# A4a_Pro_Mini.net
KiCad netlist of a schematic drawn in EAGLE
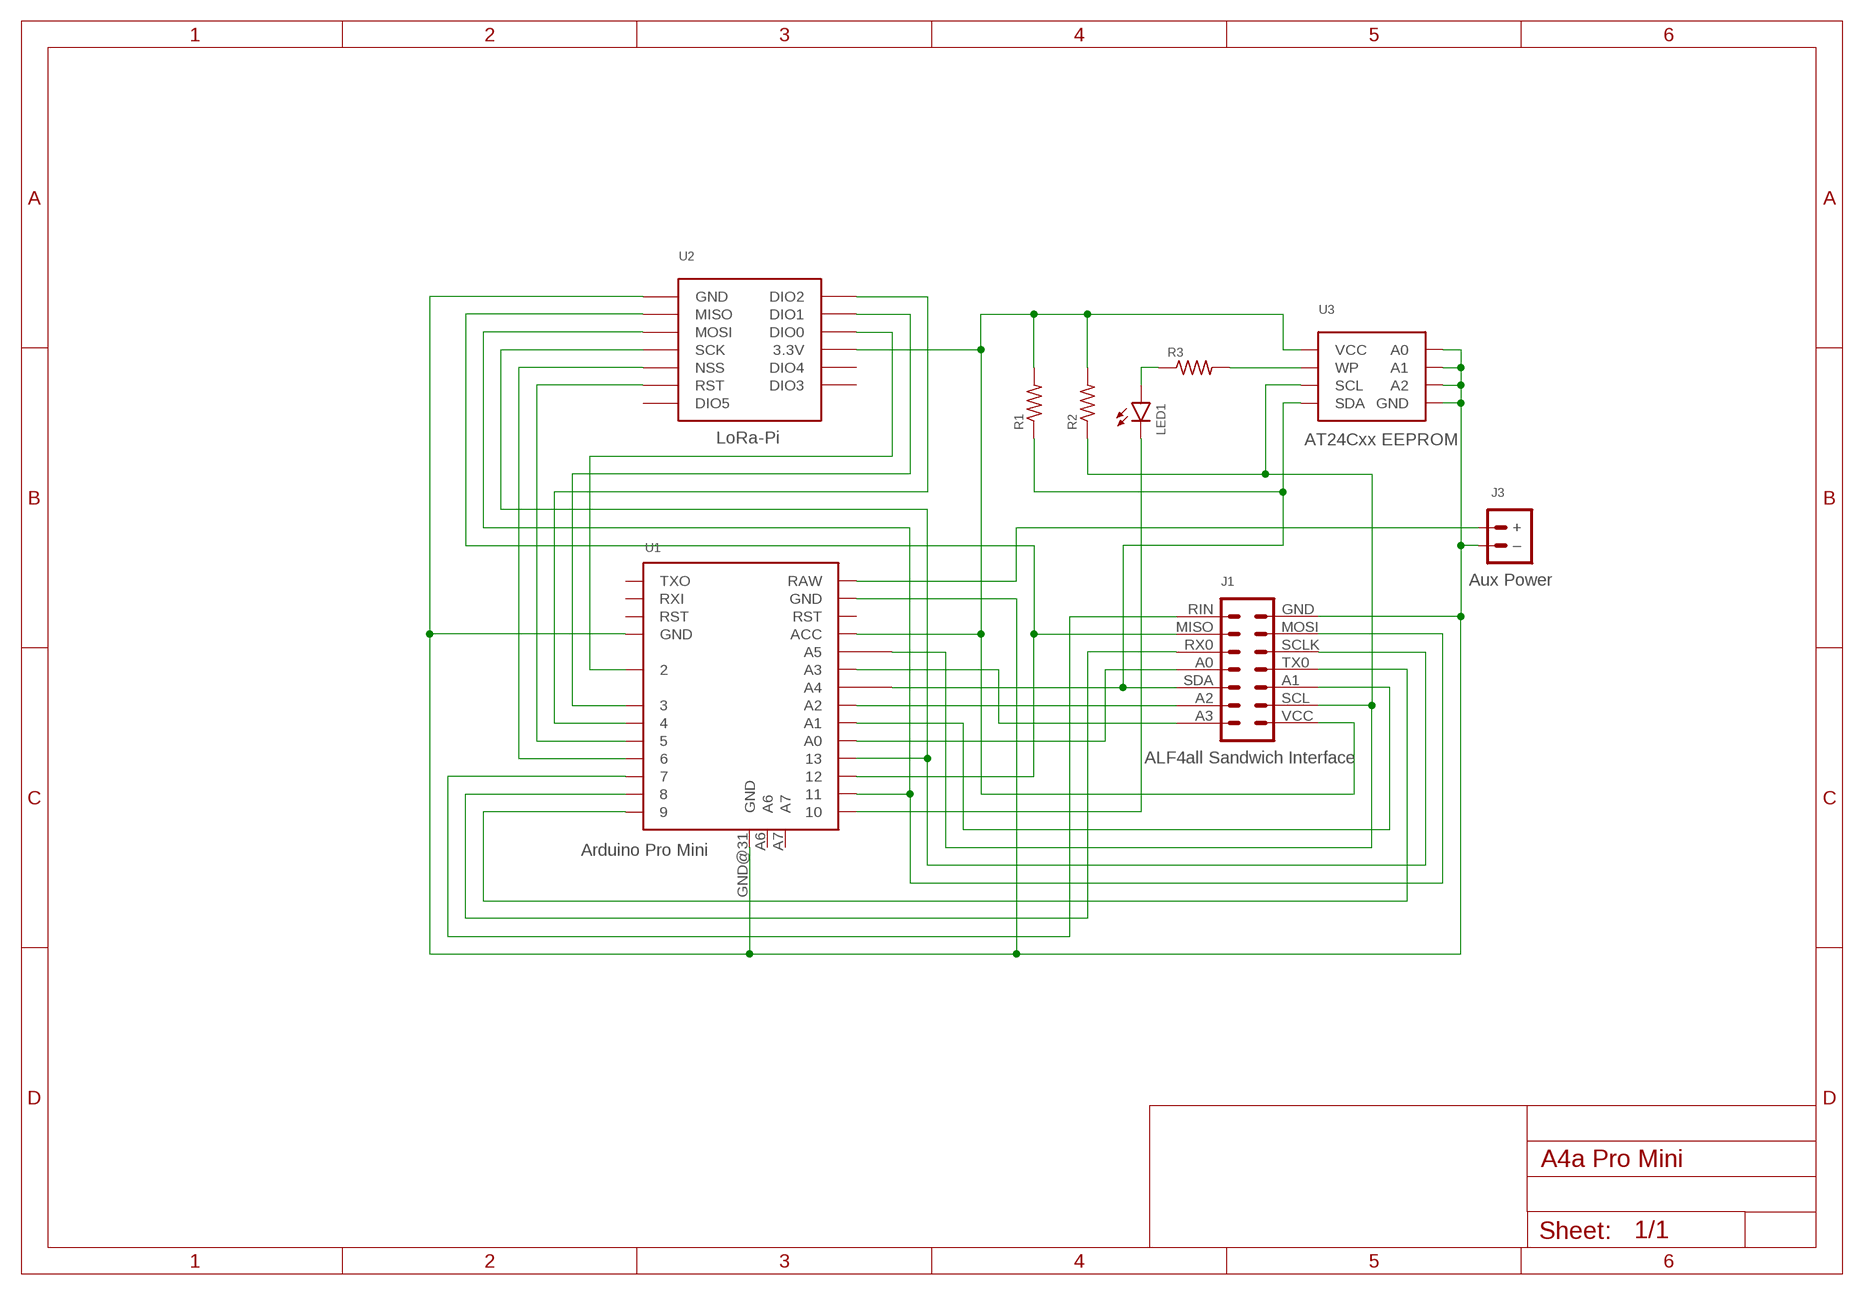
[diagram p0: schematic, sheet 1]

(export (version "E")
  (design (tool "Eeschema 10.0.6"))
  (components
    (comp (ref "J1")
      (value "ALF4all Sandwich Interface")
      (footprint "eagle-import:CONN_2X7-ALF4ALL-PROCESSOR-B")
      (libsource (lib "eagle-import") (part "HEADER-2X7-ALF4ALL-PROCESSOR-B"))
    )
    (comp (ref "J3")
      (value "Aux Power")
      (footprint "eagle-import:JST-PH2.0-2-HORIZONTAL")
      (libsource (lib "eagle-import") (part "JST-PH2.0-2-MALE-HORIZONTALJST-PTH-2"))
    )
    (comp (ref "LED1")
      (value "LEDCHIP-LED0805")
      (footprint "eagle-import:CHIP-LED0805")
      (libsource (lib "eagle-import") (part "LEDCHIP-LED0805"))
    )
    (comp (ref "R1")
      (value "RESISTORR0805")
      (footprint "eagle-import:R0805")
      (libsource (lib "eagle-import") (part "RESISTORR0805"))
    )
    (comp (ref "R2")
      (value "RESISTORR0805")
      (footprint "eagle-import:R0805")
      (libsource (lib "eagle-import") (part "RESISTORR0805"))
    )
    (comp (ref "R3")
      (value "RESISTORR0805")
      (footprint "eagle-import:R0805")
      (libsource (lib "eagle-import") (part "RESISTORR0805"))
    )
    (comp (ref "U1")
      (value "Arduino Pro Mini")
      (footprint "eagle-import:ARDUINO-PRO-MINI-35")
      (libsource (lib "eagle-import") (part "ARDUINO-PRO-MINI-35"))
    )
    (comp (ref "U2")
      (value "LoRa-Pi")
      (footprint "eagle-import:RFM95W-PI")
      (libsource (lib "eagle-import") (part "RFM95W-PI"))
    )
    (comp (ref "U3")
      (value "AT24Cxx EEPROM")
      (footprint "eagle-import:SOP-8")
      (libsource (lib "eagle-import") (part "AT24CXX-EEPROM"))
    )
  )
  (nets
    (net (code "1") (name "Net-(J1-1)") (class "Default")
      (node (ref "J1") (pin "VCC") (pinfunction "1_VCC") (pintype "passive"))
      (node (ref "R1") (pin "2") (pinfunction "2_2") (pintype "passive"))
      (node (ref "R2") (pin "2") (pinfunction "2_2") (pintype "passive"))
      (node (ref "U1") (pin "ACC") (pinfunction "ACC_ACC") (pintype "bidirectional"))
      (node (ref "U2") (pin "3V3") (pinfunction "3.3V_3V3") (pintype "power_in"))
      (node (ref "U3") (pin "P$8") (pinfunction "VCC_P$8") (pintype "bidirectional"))
    )
    (net (code "2") (name "Net-(J1-2)") (class "Default")
      (node (ref "J1") (pin "SCL") (pinfunction "2_SCL") (pintype "passive"))
      (node (ref "R2") (pin "1") (pinfunction "1_1") (pintype "passive"))
      (node (ref "U1") (pin "A5") (pinfunction "A5_A5") (pintype "bidirectional"))
      (node (ref "U3") (pin "P$6") (pinfunction "SCL_P$6") (pintype "bidirectional"))
    )
    (net (code "3") (name "Net-(J1-3)") (class "Default")
      (node (ref "J1") (pin "A1") (pinfunction "3_A1") (pintype "passive"))
      (node (ref "U1") (pin "A1") (pinfunction "A1_A1") (pintype "bidirectional"))
    )
    (net (code "4") (name "Net-(J1-4)") (class "Default")
      (node (ref "J1") (pin "TX0") (pinfunction "4_TX0") (pintype "passive"))
      (node (ref "U1") (pin "9") (pinfunction "9_9") (pintype "bidirectional"))
    )
    (net (code "5") (name "Net-(J1-5)") (class "Default")
      (node (ref "J1") (pin "SCLK") (pinfunction "5_SCLK") (pintype "passive"))
      (node (ref "U1") (pin "13") (pinfunction "13_13") (pintype "bidirectional"))
      (node (ref "U2") (pin "SCK") (pinfunction "SCK_SCK") (pintype "bidirectional"))
    )
    (net (code "6") (name "Net-(J1-6)") (class "Default")
      (node (ref "J1") (pin "MOSI") (pinfunction "6_MOSI") (pintype "passive"))
      (node (ref "U1") (pin "11") (pinfunction "11_11") (pintype "bidirectional"))
      (node (ref "U2") (pin "MOSI") (pinfunction "MOSI_MOSI") (pintype "bidirectional"))
    )
    (net (code "7") (name "Net-(J1-7)") (class "Default")
      (node (ref "J1") (pin "GND") (pinfunction "7_GND") (pintype "passive"))
      (node (ref "J3") (pin "-") (pinfunction "–_-") (pintype "power_in"))
      (node (ref "U1") (pin "GND@11") (pinfunction "GND_GND@11") (pintype "bidirectional"))
      (node (ref "U1") (pin "GND@22") (pinfunction "GND_GND@22") (pintype "bidirectional"))
      (node (ref "U1") (pin "GND@31") (pinfunction "GND_GND@31") (pintype "bidirectional"))
      (node (ref "U2") (pin "GND@3") (pinfunction "GND_GND@3") (pintype "power_in"))
      (node (ref "U2") (pin "GND@6") (pinfunction "GND_GND@6") (pintype "power_in"))
      (node (ref "U3") (pin "P$1") (pinfunction "A0_P$1") (pintype "bidirectional"))
      (node (ref "U3") (pin "P$2") (pinfunction "A1_P$2") (pintype "bidirectional"))
      (node (ref "U3") (pin "P$3") (pinfunction "A2_P$3") (pintype "bidirectional"))
      (node (ref "U3") (pin "P$4") (pinfunction "GND_P$4") (pintype "bidirectional"))
    )
    (net (code "8") (name "Net-(J1-8)") (class "Default")
      (node (ref "J1") (pin "RIN") (pinfunction "8_RIN") (pintype "passive"))
      (node (ref "U1") (pin "7") (pinfunction "7_7") (pintype "bidirectional"))
    )
    (net (code "9") (name "Net-(J1-9)") (class "Default")
      (node (ref "J1") (pin "MISO") (pinfunction "9_MISO") (pintype "passive"))
      (node (ref "U1") (pin "12") (pinfunction "12_12") (pintype "bidirectional"))
      (node (ref "U2") (pin "MISO") (pinfunction "MISO_MISO") (pintype "bidirectional"))
    )
    (net (code "10") (name "Net-(J1-10)") (class "Default")
      (node (ref "J1") (pin "RX0") (pinfunction "10_RX0") (pintype "passive"))
      (node (ref "U1") (pin "8") (pinfunction "8_8") (pintype "bidirectional"))
    )
    (net (code "11") (name "Net-(J1-11)") (class "Default")
      (node (ref "J1") (pin "A0") (pinfunction "11_A0") (pintype "passive"))
      (node (ref "U1") (pin "A0") (pinfunction "A0_A0") (pintype "bidirectional"))
    )
    (net (code "12") (name "Net-(J1-12)") (class "Default")
      (node (ref "J1") (pin "SDA") (pinfunction "12_SDA") (pintype "passive"))
      (node (ref "R1") (pin "1") (pinfunction "1_1") (pintype "passive"))
      (node (ref "U1") (pin "A4") (pinfunction "A4_A4") (pintype "bidirectional"))
      (node (ref "U3") (pin "P$5") (pinfunction "SDA_P$5") (pintype "bidirectional"))
    )
    (net (code "13") (name "Net-(J1-13)") (class "Default")
      (node (ref "J1") (pin "A2") (pinfunction "13_A2") (pintype "passive"))
      (node (ref "U1") (pin "A2") (pinfunction "A2_A2") (pintype "bidirectional"))
    )
    (net (code "14") (name "Net-(J1-14)") (class "Default")
      (node (ref "J1") (pin "A3") (pinfunction "14_A3") (pintype "passive"))
      (node (ref "U1") (pin "A3") (pinfunction "A3_A3") (pintype "bidirectional"))
    )
    (net (code "15") (name "Net-(J3-Pad+)") (class "Default")
      (node (ref "J3") (pin "+") (pinfunction "+_+") (pintype "power_in"))
      (node (ref "U1") (pin "RAW") (pinfunction "RAW_RAW") (pintype "bidirectional"))
    )
    (net (code "16") (name "Net-(LED1-PadA)") (class "Default")
      (node (ref "LED1") (pin "A") (pinfunction "A_A") (pintype "passive"))
      (node (ref "R3") (pin "1") (pinfunction "1_1") (pintype "passive"))
    )
    (net (code "17") (name "Net-(LED1-PadC)") (class "Default")
      (node (ref "LED1") (pin "C") (pinfunction "C_C") (pintype "passive"))
      (node (ref "U1") (pin "10") (pinfunction "10_10") (pintype "bidirectional"))
    )
    (net (code "18") (name "Net-(U1-Pad2)") (class "Default")
      (node (ref "U1") (pin "2") (pinfunction "2_2") (pintype "bidirectional"))
      (node (ref "U2") (pin "DIO0") (pinfunction "DIO0_DIO0") (pintype "bidirectional"))
    )
    (net (code "19") (name "Net-(U1-Pad3)") (class "Default")
      (node (ref "U1") (pin "3") (pinfunction "3_3") (pintype "bidirectional"))
      (node (ref "U2") (pin "DIO1") (pinfunction "DIO1_DIO1") (pintype "bidirectional"))
    )
    (net (code "20") (name "Net-(U1-Pad4)") (class "Default")
      (node (ref "U1") (pin "4") (pinfunction "4_4") (pintype "bidirectional"))
      (node (ref "U2") (pin "DIO2") (pinfunction "DIO2_DIO2") (pintype "bidirectional"))
    )
    (net (code "21") (name "Net-(U1-Pad5)") (class "Default")
      (node (ref "U1") (pin "5") (pinfunction "5_5") (pintype "bidirectional"))
      (node (ref "U2") (pin "RST") (pinfunction "RST_RST") (pintype "bidirectional"))
    )
    (net (code "22") (name "Net-(U1-Pad6)") (class "Default")
      (node (ref "U1") (pin "6") (pinfunction "6_6") (pintype "bidirectional"))
      (node (ref "U2") (pin "NSS") (pinfunction "NSS_NSS") (pintype "bidirectional"))
    )
    (net (code "23") (name "Net-(U3-WP)") (class "Default")
      (node (ref "R3") (pin "2") (pinfunction "2_2") (pintype "passive"))
      (node (ref "U3") (pin "P$7") (pinfunction "WP_P$7") (pintype "bidirectional"))
    )
    (net (code "24") (name "unconnected-(U1-PadA6)") (class "Default")
      (node (ref "U1") (pin "A6") (pinfunction "A6_A6") (pintype "bidirectional"))
    )
    (net (code "25") (name "unconnected-(U1-PadA7)") (class "Default")
      (node (ref "U1") (pin "A7") (pinfunction "A7_A7") (pintype "bidirectional"))
    )
    (net (code "26") (name "unconnected-(U1-RST-PadRST@10)") (class "Default")
      (node (ref "U1") (pin "RST@10") (pinfunction "RST_RST@10") (pintype "bidirectional"))
    )
    (net (code "27") (name "unconnected-(U1-RST-PadRST@21)") (class "Default")
      (node (ref "U1") (pin "RST@21") (pinfunction "RST_RST@21") (pintype "bidirectional"))
    )
    (net (code "28") (name "unconnected-(U1-RXI-PadRXI@20)") (class "Default")
      (node (ref "U1") (pin "RXI@20") (pinfunction "RXI_RXI@20") (pintype "bidirectional"))
    )
    (net (code "29") (name "unconnected-(U1-TXO-PadTXO@19)") (class "Default")
      (node (ref "U1") (pin "TXO@19") (pinfunction "TXO_TXO@19") (pintype "bidirectional"))
    )
    (net (code "30") (name "unconnected-(U2-PadDIO3)") (class "Default")
      (node (ref "U2") (pin "DIO3") (pinfunction "DIO3_DIO3") (pintype "bidirectional"))
    )
    (net (code "31") (name "unconnected-(U2-PadDIO4)") (class "Default")
      (node (ref "U2") (pin "DIO4") (pinfunction "DIO4_DIO4") (pintype "bidirectional"))
    )
    (net (code "32") (name "unconnected-(U2-PadDIO5)") (class "Default")
      (node (ref "U2") (pin "DIO5") (pinfunction "DIO5_DIO5") (pintype "bidirectional"))
    )
  )
)
